# 05-High_Speed_MUX.net
KiCad netlist of a schematic drawn in Altium Designer
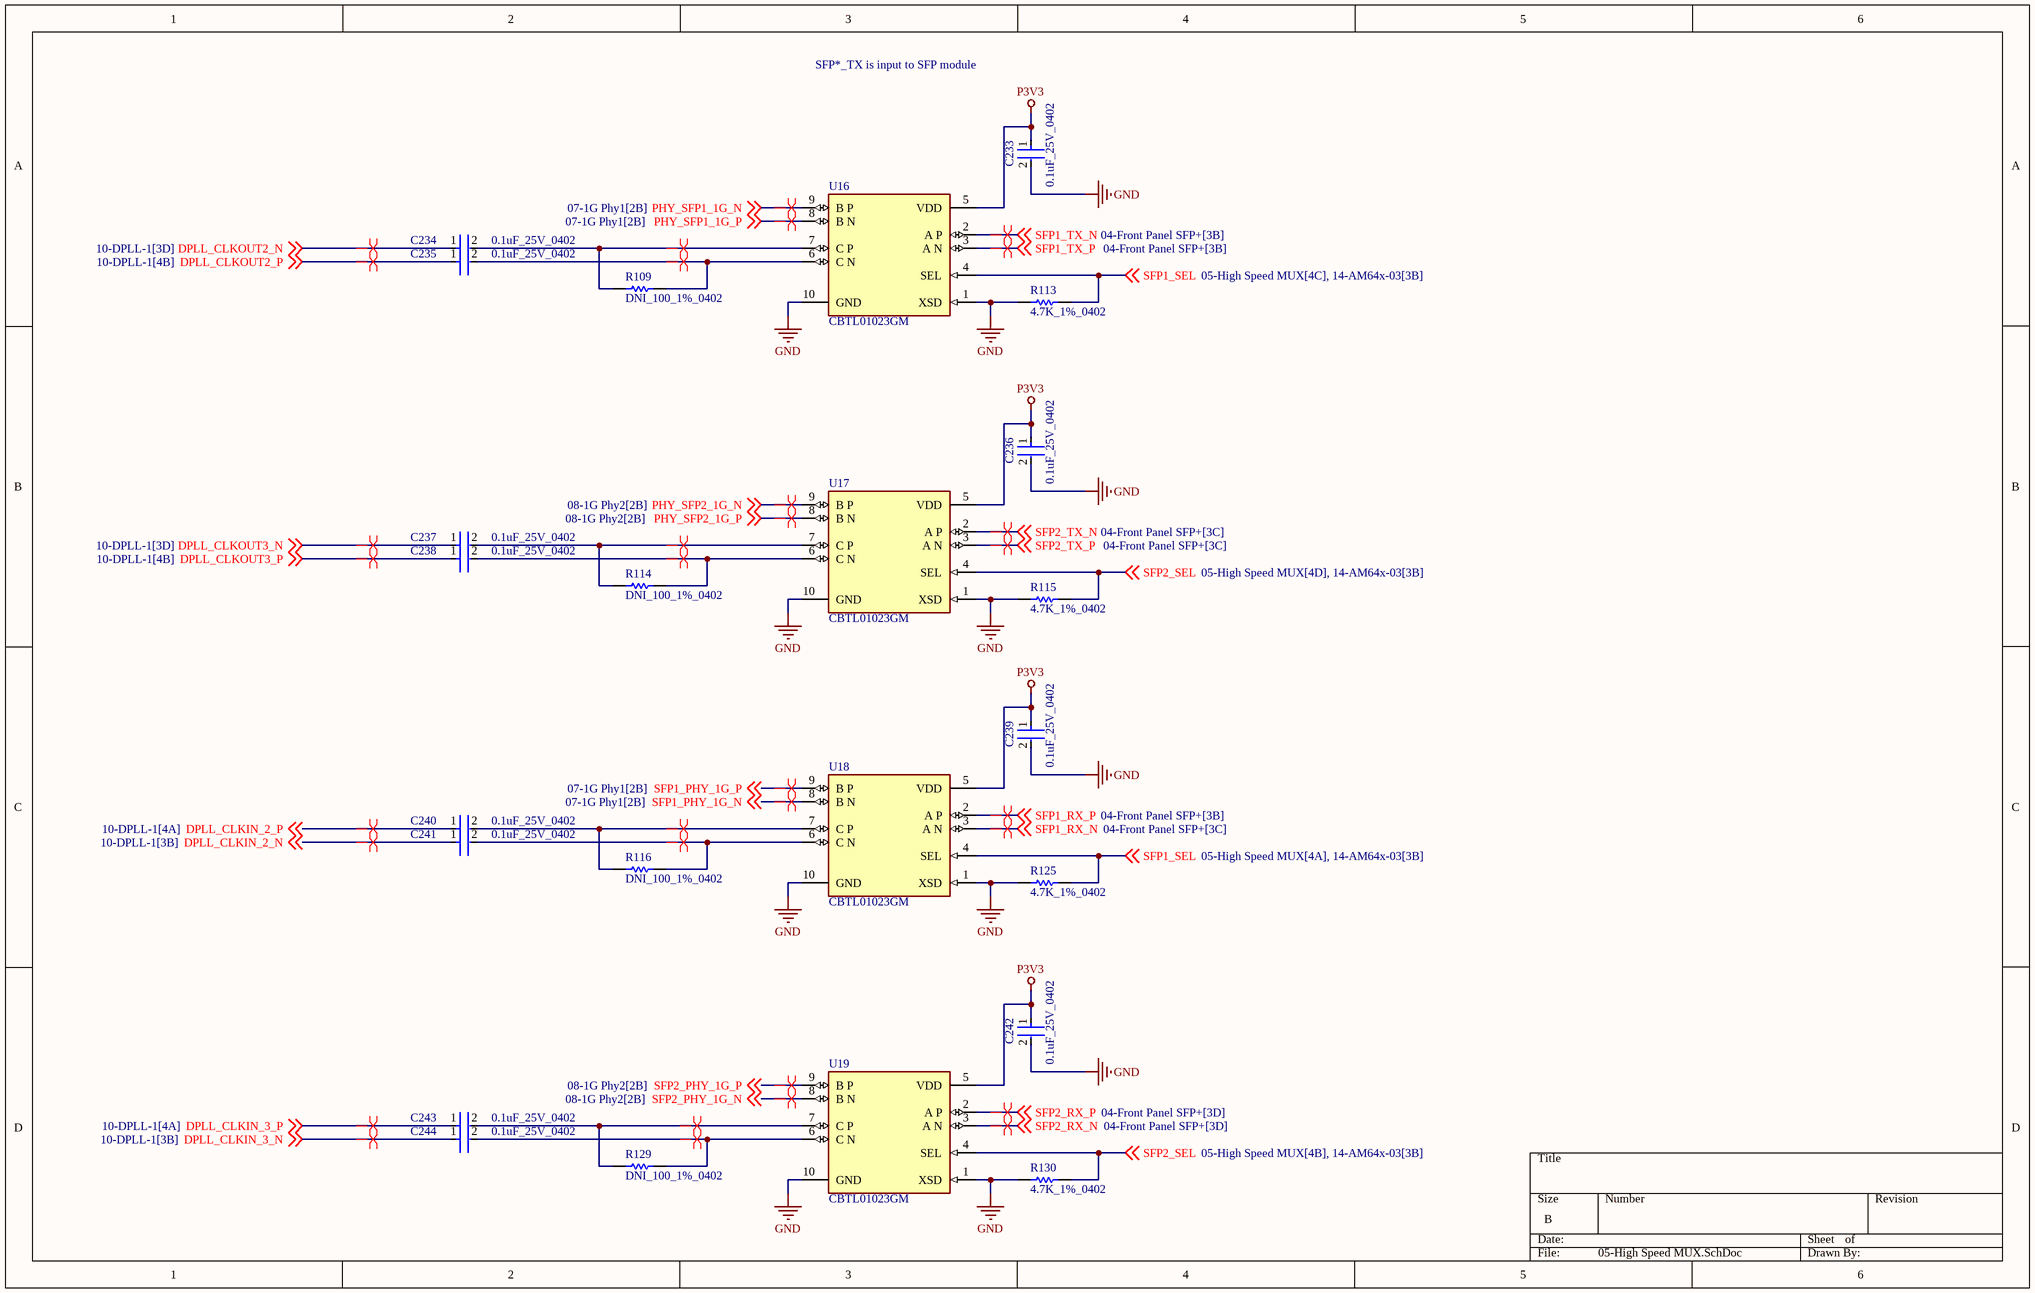
[diagram p0: 05-High Speed MUX.SchDoc]

(export (version "E")
  (design (tool "Eeschema 10.0.6"))
  (components
    (comp (ref "C233")
      (value "0.1uF_25V_0402")
      (footprint "FP-0402-L_1_0_1-W_0_5_0_1-IPC_C")
      (description "General Purpose Ceramic Capacitor, 0402, 100nF, 10%, X7R, 15%, 25V")
      (fields (field (name "VOLTAGE") "25V") (field (name "TOLERANCE") "10%"))
      (libsource (lib "Altium Content Vault") (part "b4654b650e69147ec39a6b967a45e02"))
    )
    (comp (ref "C234")
      (value "0.1uF_25V_0402")
      (footprint "FP-0402-L_1_0_1-W_0_5_0_1-IPC_C")
      (description "General Purpose Ceramic Capacitor, 0402, 100nF, 10%, X7R, 15%, 25V")
      (fields (field (name "VOLTAGE") "25V") (field (name "TOLERANCE") "10%"))
      (libsource (lib "Altium Content Vault") (part "b4654b650e69147ec39a6b967a45e02"))
    )
    (comp (ref "C235")
      (value "0.1uF_25V_0402")
      (footprint "FP-0402-L_1_0_1-W_0_5_0_1-IPC_C")
      (description "General Purpose Ceramic Capacitor, 0402, 100nF, 10%, X7R, 15%, 25V")
      (fields (field (name "VOLTAGE") "25V") (field (name "TOLERANCE") "10%"))
      (libsource (lib "Altium Content Vault") (part "b4654b650e69147ec39a6b967a45e02"))
    )
    (comp (ref "C236")
      (value "0.1uF_25V_0402")
      (footprint "FP-0402-L_1_0_1-W_0_5_0_1-IPC_C")
      (description "General Purpose Ceramic Capacitor, 0402, 100nF, 10%, X7R, 15%, 25V")
      (fields (field (name "VOLTAGE") "25V") (field (name "TOLERANCE") "10%"))
      (libsource (lib "Altium Content Vault") (part "b4654b650e69147ec39a6b967a45e02"))
    )
    (comp (ref "C237")
      (value "0.1uF_25V_0402")
      (footprint "FP-0402-L_1_0_1-W_0_5_0_1-IPC_C")
      (description "General Purpose Ceramic Capacitor, 0402, 100nF, 10%, X7R, 15%, 25V")
      (fields (field (name "VOLTAGE") "25V") (field (name "TOLERANCE") "10%"))
      (libsource (lib "Altium Content Vault") (part "b4654b650e69147ec39a6b967a45e02"))
    )
    (comp (ref "C238")
      (value "0.1uF_25V_0402")
      (footprint "FP-0402-L_1_0_1-W_0_5_0_1-IPC_C")
      (description "General Purpose Ceramic Capacitor, 0402, 100nF, 10%, X7R, 15%, 25V")
      (fields (field (name "VOLTAGE") "25V") (field (name "TOLERANCE") "10%"))
      (libsource (lib "Altium Content Vault") (part "b4654b650e69147ec39a6b967a45e02"))
    )
    (comp (ref "C239")
      (value "0.1uF_25V_0402")
      (footprint "FP-0402-L_1_0_1-W_0_5_0_1-IPC_C")
      (description "General Purpose Ceramic Capacitor, 0402, 100nF, 10%, X7R, 15%, 25V")
      (fields (field (name "VOLTAGE") "25V") (field (name "TOLERANCE") "10%"))
      (libsource (lib "Altium Content Vault") (part "b4654b650e69147ec39a6b967a45e02"))
    )
    (comp (ref "C240")
      (value "0.1uF_25V_0402")
      (footprint "FP-0402-L_1_0_1-W_0_5_0_1-IPC_C")
      (description "General Purpose Ceramic Capacitor, 0402, 100nF, 10%, X7R, 15%, 25V")
      (fields (field (name "VOLTAGE") "25V") (field (name "TOLERANCE") "10%"))
      (libsource (lib "Altium Content Vault") (part "b4654b650e69147ec39a6b967a45e02"))
    )
    (comp (ref "C241")
      (value "0.1uF_25V_0402")
      (footprint "FP-0402-L_1_0_1-W_0_5_0_1-IPC_C")
      (description "General Purpose Ceramic Capacitor, 0402, 100nF, 10%, X7R, 15%, 25V")
      (fields (field (name "VOLTAGE") "25V") (field (name "TOLERANCE") "10%"))
      (libsource (lib "Altium Content Vault") (part "b4654b650e69147ec39a6b967a45e02"))
    )
    (comp (ref "C242")
      (value "0.1uF_25V_0402")
      (footprint "FP-0402-L_1_0_1-W_0_5_0_1-IPC_C")
      (description "General Purpose Ceramic Capacitor, 0402, 100nF, 10%, X7R, 15%, 25V")
      (fields (field (name "VOLTAGE") "25V") (field (name "TOLERANCE") "10%"))
      (libsource (lib "Altium Content Vault") (part "b4654b650e69147ec39a6b967a45e02"))
    )
    (comp (ref "C243")
      (value "0.1uF_25V_0402")
      (footprint "FP-0402-L_1_0_1-W_0_5_0_1-IPC_C")
      (description "General Purpose Ceramic Capacitor, 0402, 100nF, 10%, X7R, 15%, 25V")
      (fields (field (name "VOLTAGE") "25V") (field (name "TOLERANCE") "10%"))
      (libsource (lib "Altium Content Vault") (part "b4654b650e69147ec39a6b967a45e02"))
    )
    (comp (ref "C244")
      (value "0.1uF_25V_0402")
      (footprint "FP-0402-L_1_0_1-W_0_5_0_1-IPC_C")
      (description "General Purpose Ceramic Capacitor, 0402, 100nF, 10%, X7R, 15%, 25V")
      (fields (field (name "VOLTAGE") "25V") (field (name "TOLERANCE") "10%"))
      (libsource (lib "Altium Content Vault") (part "b4654b650e69147ec39a6b967a45e02"))
    )
    (comp (ref "R109")
      (value "DNI_100_1%_0402")
      (footprint "RESC1005X40X25LL05T10")
      (fields (field (name "MANUFACTURER") "Vishay Dale") (field (name "PART NUMBER") "CRCW0402100RFKEDHP"))
      (libsource (lib "Altium Content Vault") (part "RES"))
    )
    (comp (ref "R113")
      (value "4.7K_1%_0402")
      (footprint "RESC1005X40X25NL10T10")
      (fields (field (name "MANUFACTURER") "Bourns") (field (name "PART NUMBER") "CR0402-FX-4701GLF"))
      (libsource (lib "Altium Content Vault") (part "RES"))
    )
    (comp (ref "R114")
      (value "DNI_100_1%_0402")
      (footprint "RESC1005X40X25LL05T10")
      (fields (field (name "MANUFACTURER") "Vishay Dale") (field (name "PART NUMBER") "CRCW0402100RFKEDHP"))
      (libsource (lib "Altium Content Vault") (part "RES"))
    )
    (comp (ref "R115")
      (value "4.7K_1%_0402")
      (footprint "RESC1005X40X25NL10T10")
      (fields (field (name "MANUFACTURER") "Bourns") (field (name "PART NUMBER") "CR0402-FX-4701GLF"))
      (libsource (lib "Altium Content Vault") (part "RES"))
    )
    (comp (ref "R116")
      (value "DNI_100_1%_0402")
      (footprint "RESC1005X40X25LL05T10")
      (fields (field (name "MANUFACTURER") "Vishay Dale") (field (name "PART NUMBER") "CRCW0402100RFKEDHP"))
      (libsource (lib "Altium Content Vault") (part "RES"))
    )
    (comp (ref "R125")
      (value "4.7K_1%_0402")
      (footprint "RESC1005X40X25NL10T10")
      (fields (field (name "MANUFACTURER") "Bourns") (field (name "PART NUMBER") "CR0402-FX-4701GLF"))
      (libsource (lib "Altium Content Vault") (part "RES"))
    )
    (comp (ref "R129")
      (value "DNI_100_1%_0402")
      (footprint "RESC1005X40X25LL05T10")
      (fields (field (name "MANUFACTURER") "Vishay Dale") (field (name "PART NUMBER") "CRCW0402100RFKEDHP"))
      (libsource (lib "Altium Content Vault") (part "RES"))
    )
    (comp (ref "R130")
      (value "4.7K_1%_0402")
      (footprint "RESC1005X40X25NL10T10")
      (fields (field (name "MANUFACTURER") "Bourns") (field (name "PART NUMBER") "CR0402-FX-4701GLF"))
      (libsource (lib "Altium Content Vault") (part "RES"))
    )
    (comp (ref "U16")
      (value "CBTL01023GM")
      (footprint "FP-SOT1049-3-MFG")
      (description "DisplayPort, PCIe, USB Switch IC 1 Channel 10-XQFN (1.55x2)")
      (libsource (lib "Altium Content Vault") (part "e9da46103f78ef6d78ad37aaf3bfac1"))
    )
    (comp (ref "U17")
      (value "CBTL01023GM")
      (footprint "FP-SOT1049-3-MFG")
      (description "DisplayPort, PCIe, USB Switch IC 1 Channel 10-XQFN (1.55x2)")
      (libsource (lib "Altium Content Vault") (part "e9da46103f78ef6d78ad37aaf3bfac1"))
    )
    (comp (ref "U18")
      (value "CBTL01023GM")
      (footprint "FP-SOT1049-3-MFG")
      (description "DisplayPort, PCIe, USB Switch IC 1 Channel 10-XQFN (1.55x2)")
      (libsource (lib "Altium Content Vault") (part "e9da46103f78ef6d78ad37aaf3bfac1"))
    )
    (comp (ref "U19")
      (value "CBTL01023GM")
      (footprint "FP-SOT1049-3-MFG")
      (description "DisplayPort, PCIe, USB Switch IC 1 Channel 10-XQFN (1.55x2)")
      (libsource (lib "Altium Content Vault") (part "e9da46103f78ef6d78ad37aaf3bfac1"))
    )
  )
  (nets
    (net (code "1") (name "DPLL_CLKIN_2_N") (class "Default")
      (node (ref "C241") (pin "1") (pinfunction "1_1") (pintype "passive"))
    )
    (net (code "2") (name "DPLL_CLKIN_2_P") (class "Default")
      (node (ref "C240") (pin "1") (pinfunction "1_1") (pintype "passive"))
    )
    (net (code "3") (name "DPLL_CLKIN_3_N") (class "Default")
      (node (ref "C244") (pin "1") (pinfunction "1_1") (pintype "passive"))
    )
    (net (code "4") (name "DPLL_CLKIN_3_P") (class "Default")
      (node (ref "C243") (pin "1") (pinfunction "1_1") (pintype "passive"))
    )
    (net (code "5") (name "DPLL_CLKOUT2_N") (class "Default")
      (node (ref "C234") (pin "1") (pinfunction "1_1") (pintype "passive"))
    )
    (net (code "6") (name "DPLL_CLKOUT2_P") (class "Default")
      (node (ref "C235") (pin "1") (pinfunction "1_1") (pintype "passive"))
    )
    (net (code "7") (name "DPLL_CLKOUT3_N") (class "Default")
      (node (ref "C237") (pin "1") (pinfunction "1_1") (pintype "passive"))
    )
    (net (code "8") (name "DPLL_CLKOUT3_P") (class "Default")
      (node (ref "C238") (pin "1") (pinfunction "1_1") (pintype "passive"))
    )
    (net (code "9") (name "GND") (class "Default")
      (node (ref "C233") (pin "2") (pinfunction "2_2") (pintype "passive"))
      (node (ref "C236") (pin "2") (pinfunction "2_2") (pintype "passive"))
      (node (ref "C239") (pin "2") (pinfunction "2_2") (pintype "passive"))
      (node (ref "C242") (pin "2") (pinfunction "2_2") (pintype "passive"))
      (node (ref "R113") (pin "1") (pinfunction "1_1") (pintype "passive"))
      (node (ref "R115") (pin "1") (pinfunction "1_1") (pintype "passive"))
      (node (ref "R125") (pin "1") (pinfunction "1_1") (pintype "passive"))
      (node (ref "R130") (pin "1") (pinfunction "1_1") (pintype "passive"))
      (node (ref "U16") (pin "1") (pinfunction "XSD_1") (pintype "input"))
      (node (ref "U16") (pin "10") (pinfunction "GND_10") (pintype "power_in"))
      (node (ref "U17") (pin "1") (pinfunction "XSD_1") (pintype "input"))
      (node (ref "U17") (pin "10") (pinfunction "GND_10") (pintype "power_in"))
      (node (ref "U18") (pin "1") (pinfunction "XSD_1") (pintype "input"))
      (node (ref "U18") (pin "10") (pinfunction "GND_10") (pintype "power_in"))
      (node (ref "U19") (pin "1") (pinfunction "XSD_1") (pintype "input"))
      (node (ref "U19") (pin "10") (pinfunction "GND_10") (pintype "power_in"))
    )
    (net (code "10") (name "Net-(U16-C_N)") (class "Default")
      (node (ref "C235") (pin "2") (pinfunction "2_2") (pintype "passive"))
      (node (ref "R109") (pin "2") (pinfunction "2_2") (pintype "passive"))
      (node (ref "U16") (pin "6") (pinfunction "C_N_6") (pintype "bidirectional"))
    )
    (net (code "11") (name "Net-(U16-C_P)") (class "Default")
      (node (ref "C234") (pin "2") (pinfunction "2_2") (pintype "passive"))
      (node (ref "R109") (pin "1") (pinfunction "1_1") (pintype "passive"))
      (node (ref "U16") (pin "7") (pinfunction "C_P_7") (pintype "bidirectional"))
    )
    (net (code "12") (name "Net-(U17-C_N)") (class "Default")
      (node (ref "C238") (pin "2") (pinfunction "2_2") (pintype "passive"))
      (node (ref "R114") (pin "2") (pinfunction "2_2") (pintype "passive"))
      (node (ref "U17") (pin "6") (pinfunction "C_N_6") (pintype "bidirectional"))
    )
    (net (code "13") (name "Net-(U17-C_P)") (class "Default")
      (node (ref "C237") (pin "2") (pinfunction "2_2") (pintype "passive"))
      (node (ref "R114") (pin "1") (pinfunction "1_1") (pintype "passive"))
      (node (ref "U17") (pin "7") (pinfunction "C_P_7") (pintype "bidirectional"))
    )
    (net (code "14") (name "Net-(U18-C_N)") (class "Default")
      (node (ref "C241") (pin "2") (pinfunction "2_2") (pintype "passive"))
      (node (ref "R116") (pin "2") (pinfunction "2_2") (pintype "passive"))
      (node (ref "U18") (pin "6") (pinfunction "C_N_6") (pintype "bidirectional"))
    )
    (net (code "15") (name "Net-(U18-C_P)") (class "Default")
      (node (ref "C240") (pin "2") (pinfunction "2_2") (pintype "passive"))
      (node (ref "R116") (pin "1") (pinfunction "1_1") (pintype "passive"))
      (node (ref "U18") (pin "7") (pinfunction "C_P_7") (pintype "bidirectional"))
    )
    (net (code "16") (name "Net-(U19-C_N)") (class "Default")
      (node (ref "C244") (pin "2") (pinfunction "2_2") (pintype "passive"))
      (node (ref "R129") (pin "2") (pinfunction "2_2") (pintype "passive"))
      (node (ref "U19") (pin "6") (pinfunction "C_N_6") (pintype "bidirectional"))
    )
    (net (code "17") (name "Net-(U19-C_P)") (class "Default")
      (node (ref "C243") (pin "2") (pinfunction "2_2") (pintype "passive"))
      (node (ref "R129") (pin "1") (pinfunction "1_1") (pintype "passive"))
      (node (ref "U19") (pin "7") (pinfunction "C_P_7") (pintype "bidirectional"))
    )
    (net (code "18") (name "P3V3") (class "Default")
      (node (ref "C233") (pin "1") (pinfunction "1_1") (pintype "passive"))
      (node (ref "C236") (pin "1") (pinfunction "1_1") (pintype "passive"))
      (node (ref "C239") (pin "1") (pinfunction "1_1") (pintype "passive"))
      (node (ref "C242") (pin "1") (pinfunction "1_1") (pintype "passive"))
      (node (ref "U16") (pin "5") (pinfunction "VDD_5") (pintype "power_in"))
      (node (ref "U17") (pin "5") (pinfunction "VDD_5") (pintype "power_in"))
      (node (ref "U18") (pin "5") (pinfunction "VDD_5") (pintype "power_in"))
      (node (ref "U19") (pin "5") (pinfunction "VDD_5") (pintype "power_in"))
    )
    (net (code "19") (name "PHY_SFP1_1G_N") (class "Default")
      (node (ref "U16") (pin "9") (pinfunction "B_P_9") (pintype "bidirectional"))
    )
    (net (code "20") (name "PHY_SFP1_1G_P") (class "Default")
      (node (ref "U16") (pin "8") (pinfunction "B_N_8") (pintype "bidirectional"))
    )
    (net (code "21") (name "PHY_SFP2_1G_N") (class "Default")
      (node (ref "U17") (pin "9") (pinfunction "B_P_9") (pintype "bidirectional"))
    )
    (net (code "22") (name "PHY_SFP2_1G_P") (class "Default")
      (node (ref "U17") (pin "8") (pinfunction "B_N_8") (pintype "bidirectional"))
    )
    (net (code "23") (name "SFP1_PHY_1G_N") (class "Default")
      (node (ref "U18") (pin "8") (pinfunction "B_N_8") (pintype "bidirectional"))
    )
    (net (code "24") (name "SFP1_PHY_1G_P") (class "Default")
      (node (ref "U18") (pin "9") (pinfunction "B_P_9") (pintype "bidirectional"))
    )
    (net (code "25") (name "SFP1_RX_N") (class "Default")
      (node (ref "U18") (pin "3") (pinfunction "A_N_3") (pintype "bidirectional"))
    )
    (net (code "26") (name "SFP1_RX_P") (class "Default")
      (node (ref "U18") (pin "2") (pinfunction "A_P_2") (pintype "bidirectional"))
    )
    (net (code "27") (name "SFP1_SEL") (class "Default")
      (node (ref "R113") (pin "2") (pinfunction "2_2") (pintype "passive"))
      (node (ref "R125") (pin "2") (pinfunction "2_2") (pintype "passive"))
      (node (ref "U16") (pin "4") (pinfunction "SEL_4") (pintype "input"))
      (node (ref "U18") (pin "4") (pinfunction "SEL_4") (pintype "input"))
    )
    (net (code "28") (name "SFP1_TX_N") (class "Default")
      (node (ref "U16") (pin "2") (pinfunction "A_P_2") (pintype "bidirectional"))
    )
    (net (code "29") (name "SFP1_TX_P") (class "Default")
      (node (ref "U16") (pin "3") (pinfunction "A_N_3") (pintype "bidirectional"))
    )
    (net (code "30") (name "SFP2_PHY_1G_N") (class "Default")
      (node (ref "U19") (pin "8") (pinfunction "B_N_8") (pintype "bidirectional"))
    )
    (net (code "31") (name "SFP2_PHY_1G_P") (class "Default")
      (node (ref "U19") (pin "9") (pinfunction "B_P_9") (pintype "bidirectional"))
    )
    (net (code "32") (name "SFP2_RX_N") (class "Default")
      (node (ref "U19") (pin "3") (pinfunction "A_N_3") (pintype "bidirectional"))
    )
    (net (code "33") (name "SFP2_RX_P") (class "Default")
      (node (ref "U19") (pin "2") (pinfunction "A_P_2") (pintype "bidirectional"))
    )
    (net (code "34") (name "SFP2_SEL") (class "Default")
      (node (ref "R115") (pin "2") (pinfunction "2_2") (pintype "passive"))
      (node (ref "R130") (pin "2") (pinfunction "2_2") (pintype "passive"))
      (node (ref "U17") (pin "4") (pinfunction "SEL_4") (pintype "input"))
      (node (ref "U19") (pin "4") (pinfunction "SEL_4") (pintype "input"))
    )
    (net (code "35") (name "SFP2_TX_N") (class "Default")
      (node (ref "U17") (pin "2") (pinfunction "A_P_2") (pintype "bidirectional"))
    )
    (net (code "36") (name "SFP2_TX_P") (class "Default")
      (node (ref "U17") (pin "3") (pinfunction "A_N_3") (pintype "bidirectional"))
    )
  )
)
